# TS3USBCA410_USB_C_SBU_Multiplexer.net
KiCad netlist of a schematic drawn in Altium Designer
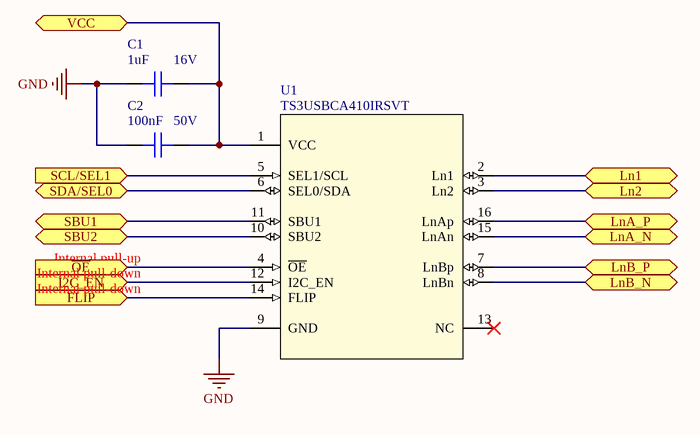
[diagram p0: TS3USBCA410_USB_C_SBU_Multiplexer.SchDoc]

(export (version "E")
  (design (tool "Eeschema 10.0.6"))
  (components
    (comp (ref "C1")
      (value "CAP CER 1UF 16V X5R 0402")
      (footprint "C0402")
      (description "1µF ±10% 16V Ceramic Capacitor X5R 0402 (1005 Metric)")
      (fields
        (field (name "MANUFACTURER") "Yageo")
        (field (name "MANUFACTURER PART NUMBER") "CC0402KRX5R7BB105")
        (field (name "CAPACITANCE") "1uF")
        (field (name "VOLTAGE RATING") "16V")
      )
      (libsource (lib "capacitors_smd") (part "CAP CER 1UF 16V X5R 0402"))
    )
    (comp (ref "C2")
      (value "CAP CER 0.1UF 50V X7R 0402")
      (footprint "C0402")
      (description "0.1µF ±10% 50V Ceramic Capacitor X7R 0402 (1005 Metric)")
      (fields
        (field (name "MANUFACTURER") "TDK")
        (field (name "MANUFACTURER PART NUMBER") "CGA2B3X7R1H104K050BB")
        (field (name "CAPACITANCE") "100nF")
        (field (name "VOLTAGE") "50V")
      )
      (libsource (lib "capacitors_smd") (part "CAP CER 0.1UF 50V X7R 0402"))
    )
    (comp (ref "U1")
      (value "TS3USBCA410IRSVT")
      (footprint "RSV16_TEX")
      (description "USB Switch IC 1 Channel 16-UQFN (2.6x1.8)")
      (fields (field (name "MANUFACTURER") "Texas Instruments"))
      (libsource (lib "BLDC_Motor_Driver") (part "IC TS3USBCA410IRSVT SBU MUX 3TO1 W/ MIC AND GNDIND T"))
    )
  )
  (nets
    (net (code "1") (name "/FLIP") (class "Default")
      (node (ref "U1") (pin "14") (pinfunction "FLIP_14") (pintype "input"))
    )
    (net (code "2") (name "/I2C_EN") (class "Default")
      (node (ref "U1") (pin "12") (pinfunction "I2C_EN_12") (pintype "input"))
    )
    (net (code "3") (name "/Ln1") (class "Default")
      (node (ref "U1") (pin "2") (pinfunction "Ln1_2") (pintype "bidirectional"))
    )
    (net (code "4") (name "/Ln2") (class "Default")
      (node (ref "U1") (pin "3") (pinfunction "Ln2_3") (pintype "bidirectional"))
    )
    (net (code "5") (name "/LnA_N") (class "Default")
      (node (ref "U1") (pin "15") (pinfunction "LnAn_15") (pintype "bidirectional"))
    )
    (net (code "6") (name "/LnA_P") (class "Default")
      (node (ref "U1") (pin "16") (pinfunction "LnAp_16") (pintype "bidirectional"))
    )
    (net (code "7") (name "/LnB_N") (class "Default")
      (node (ref "U1") (pin "8") (pinfunction "LnBn_8") (pintype "bidirectional"))
    )
    (net (code "8") (name "/LnB_P") (class "Default")
      (node (ref "U1") (pin "7") (pinfunction "LnBp_7") (pintype "bidirectional"))
    )
    (net (code "9") (name "/OE") (class "Default")
      (node (ref "U1") (pin "4") (pinfunction "OE_4") (pintype "input"))
    )
    (net (code "10") (name "/SBU1") (class "Default")
      (node (ref "U1") (pin "11") (pinfunction "SBU1_11") (pintype "bidirectional"))
    )
    (net (code "11") (name "/SBU2") (class "Default")
      (node (ref "U1") (pin "10") (pinfunction "SBU2_10") (pintype "bidirectional"))
    )
    (net (code "12") (name "/SCL{slash}SEL1") (class "Default")
      (node (ref "U1") (pin "5") (pinfunction "SEL1/SCL_5") (pintype "input"))
    )
    (net (code "13") (name "/SDA{slash}SEL0") (class "Default")
      (node (ref "U1") (pin "6") (pinfunction "SEL0/SDA_6") (pintype "bidirectional"))
    )
    (net (code "14") (name "/VCC") (class "Default")
      (node (ref "C1") (pin "1") (pinfunction "1_1") (pintype "passive"))
      (node (ref "C2") (pin "1") (pinfunction "1_1") (pintype "passive"))
      (node (ref "U1") (pin "1") (pinfunction "VCC_1") (pintype "power_in"))
    )
    (net (code "15") (name "GND") (class "Default")
      (node (ref "C1") (pin "2") (pinfunction "2_2") (pintype "passive"))
      (node (ref "C2") (pin "2") (pinfunction "2_2") (pintype "passive"))
      (node (ref "U1") (pin "9") (pinfunction "GND_9") (pintype "power_in"))
    )
    (net (code "16") (name "unconnected-(U1-NC-Pad13)") (class "Default")
      (node (ref "U1") (pin "13") (pinfunction "NC_13") (pintype "passive+no_connect"))
    )
  )
)
